# Button_Block.net
KiCad netlist of a schematic drawn in Altium Designer
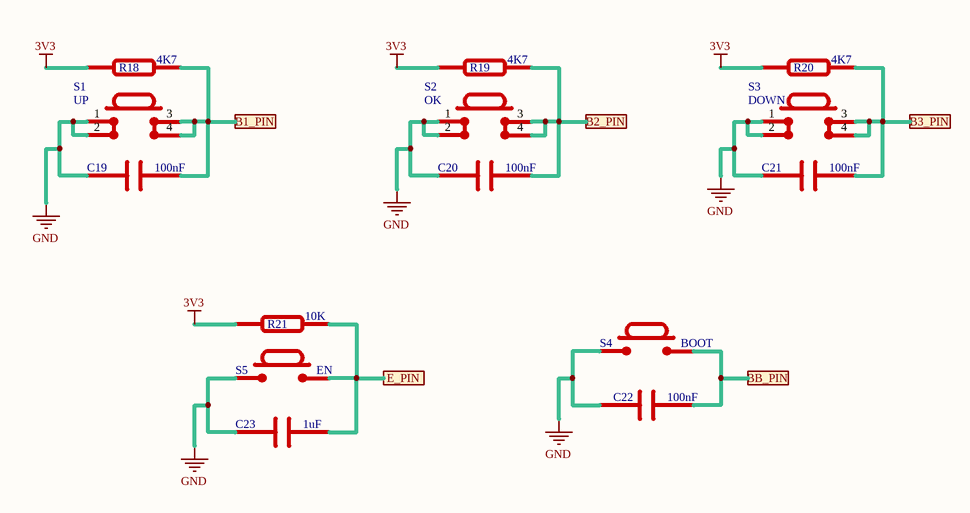
[diagram p0: Button_Block.SchDoc]

(export (version "E")
  (design (tool "Eeschema 10.0.6"))
  (components
    (comp (ref "C19")
      (value "100nF")
      (footprint "C0805")
      (description "Ceramic Capacitor")
      (libsource (lib "CTAI-Library") (part "CAP-CER"))
    )
    (comp (ref "C20")
      (value "100nF")
      (footprint "C0805")
      (description "Ceramic Capacitor")
      (libsource (lib "CTAI-Library") (part "CAP-CER"))
    )
    (comp (ref "C21")
      (value "100nF")
      (footprint "C0805")
      (description "Ceramic Capacitor")
      (libsource (lib "CTAI-Library") (part "CAP-CER"))
    )
    (comp (ref "C22")
      (value "100nF")
      (footprint "C0805")
      (description "Ceramic Capacitor")
      (libsource (lib "CTAI-Library") (part "CAP-CER"))
    )
    (comp (ref "C23")
      (value "1uF")
      (footprint "C0805")
      (description "Ceramic Capacitor")
      (libsource (lib "CTAI-Library") (part "CAP-CER"))
    )
    (comp (ref "R18")
      (value "4K7")
      (footprint "R0603")
      (description "Resistor")
      (libsource (lib "CTAI-Library") (part "Resistor"))
    )
    (comp (ref "R19")
      (value "4K7")
      (footprint "R0603")
      (description "Resistor")
      (libsource (lib "CTAI-Library") (part "Resistor"))
    )
    (comp (ref "R20")
      (value "4K7")
      (footprint "R0603")
      (description "Resistor")
      (libsource (lib "CTAI-Library") (part "Resistor"))
    )
    (comp (ref "R21")
      (value "10K")
      (footprint "R0603")
      (description "Resistor")
      (libsource (lib "CTAI-Library") (part "Resistor"))
    )
    (comp (ref "S1")
      (value "UP")
      (footprint "BTN-TH-6x6")
      (description "Tactile Switch 4 pole")
      (libsource (lib "CTAI-Library") (part "Button-4P"))
    )
    (comp (ref "S2")
      (value "OK")
      (footprint "BTN-TH-6x6")
      (description "Tactile Switch 4 pole")
      (libsource (lib "CTAI-Library") (part "Button-4P"))
    )
    (comp (ref "S3")
      (value "DOWN")
      (footprint "BTN-TH-6x6")
      (description "Tactile Switch 4 pole")
      (libsource (lib "CTAI-Library") (part "Button-4P"))
    )
    (comp (ref "S4")
      (value "BOOT")
      (footprint "BTN-SMD-3x6")
      (description "Tactile Switch 2 pole")
      (libsource (lib "CTAI-Library") (part "Button-2P"))
    )
    (comp (ref "S5")
      (value "EN")
      (footprint "BTN-SMD-3x6")
      (description "Tactile Switch 2 pole")
      (libsource (lib "CTAI-Library") (part "Button-2P"))
    )
  )
  (nets
    (net (code "1") (name "/B1_PIN") (class "Default")
      (node (ref "C19") (pin "1") (pintype "passive"))
      (node (ref "R18") (pin "1") (pinfunction "1_1") (pintype "passive"))
      (node (ref "S1") (pin "3") (pintype "passive"))
      (node (ref "S1") (pin "4") (pintype "passive"))
    )
    (net (code "2") (name "/B2_PIN") (class "Default")
      (node (ref "C20") (pin "1") (pintype "passive"))
      (node (ref "R19") (pin "1") (pinfunction "1_1") (pintype "passive"))
      (node (ref "S2") (pin "3") (pintype "passive"))
      (node (ref "S2") (pin "4") (pintype "passive"))
    )
    (net (code "3") (name "/B3_PIN") (class "Default")
      (node (ref "C21") (pin "1") (pintype "passive"))
      (node (ref "R20") (pin "1") (pinfunction "1_1") (pintype "passive"))
      (node (ref "S3") (pin "3") (pintype "passive"))
      (node (ref "S3") (pin "4") (pintype "passive"))
    )
    (net (code "4") (name "/BB_PIN") (class "Default")
      (node (ref "C22") (pin "1") (pintype "passive"))
      (node (ref "S4") (pin "2") (pintype "passive"))
    )
    (net (code "5") (name "/E_PIN") (class "Default")
      (node (ref "C23") (pin "1") (pintype "passive"))
      (node (ref "R21") (pin "1") (pinfunction "1_1") (pintype "passive"))
      (node (ref "S5") (pin "2") (pintype "passive"))
    )
    (net (code "6") (name "3V3") (class "Default")
      (node (ref "R18") (pin "2") (pinfunction "2_2") (pintype "passive"))
      (node (ref "R19") (pin "2") (pinfunction "2_2") (pintype "passive"))
      (node (ref "R20") (pin "2") (pinfunction "2_2") (pintype "passive"))
      (node (ref "R21") (pin "2") (pinfunction "2_2") (pintype "passive"))
    )
    (net (code "7") (name "GND") (class "Default")
      (node (ref "C19") (pin "2") (pintype "passive"))
      (node (ref "C20") (pin "2") (pintype "passive"))
      (node (ref "C21") (pin "2") (pintype "passive"))
      (node (ref "C22") (pin "2") (pintype "passive"))
      (node (ref "C23") (pin "2") (pintype "passive"))
      (node (ref "S1") (pin "1") (pintype "passive"))
      (node (ref "S1") (pin "2") (pintype "passive"))
      (node (ref "S2") (pin "1") (pintype "passive"))
      (node (ref "S2") (pin "2") (pintype "passive"))
      (node (ref "S3") (pin "1") (pintype "passive"))
      (node (ref "S3") (pin "2") (pintype "passive"))
      (node (ref "S4") (pin "1") (pintype "passive"))
      (node (ref "S5") (pin "1") (pintype "passive"))
    )
  )
)
